# 3_channel_relay.net
KiCad netlist of a schematic drawn in Altium Designer
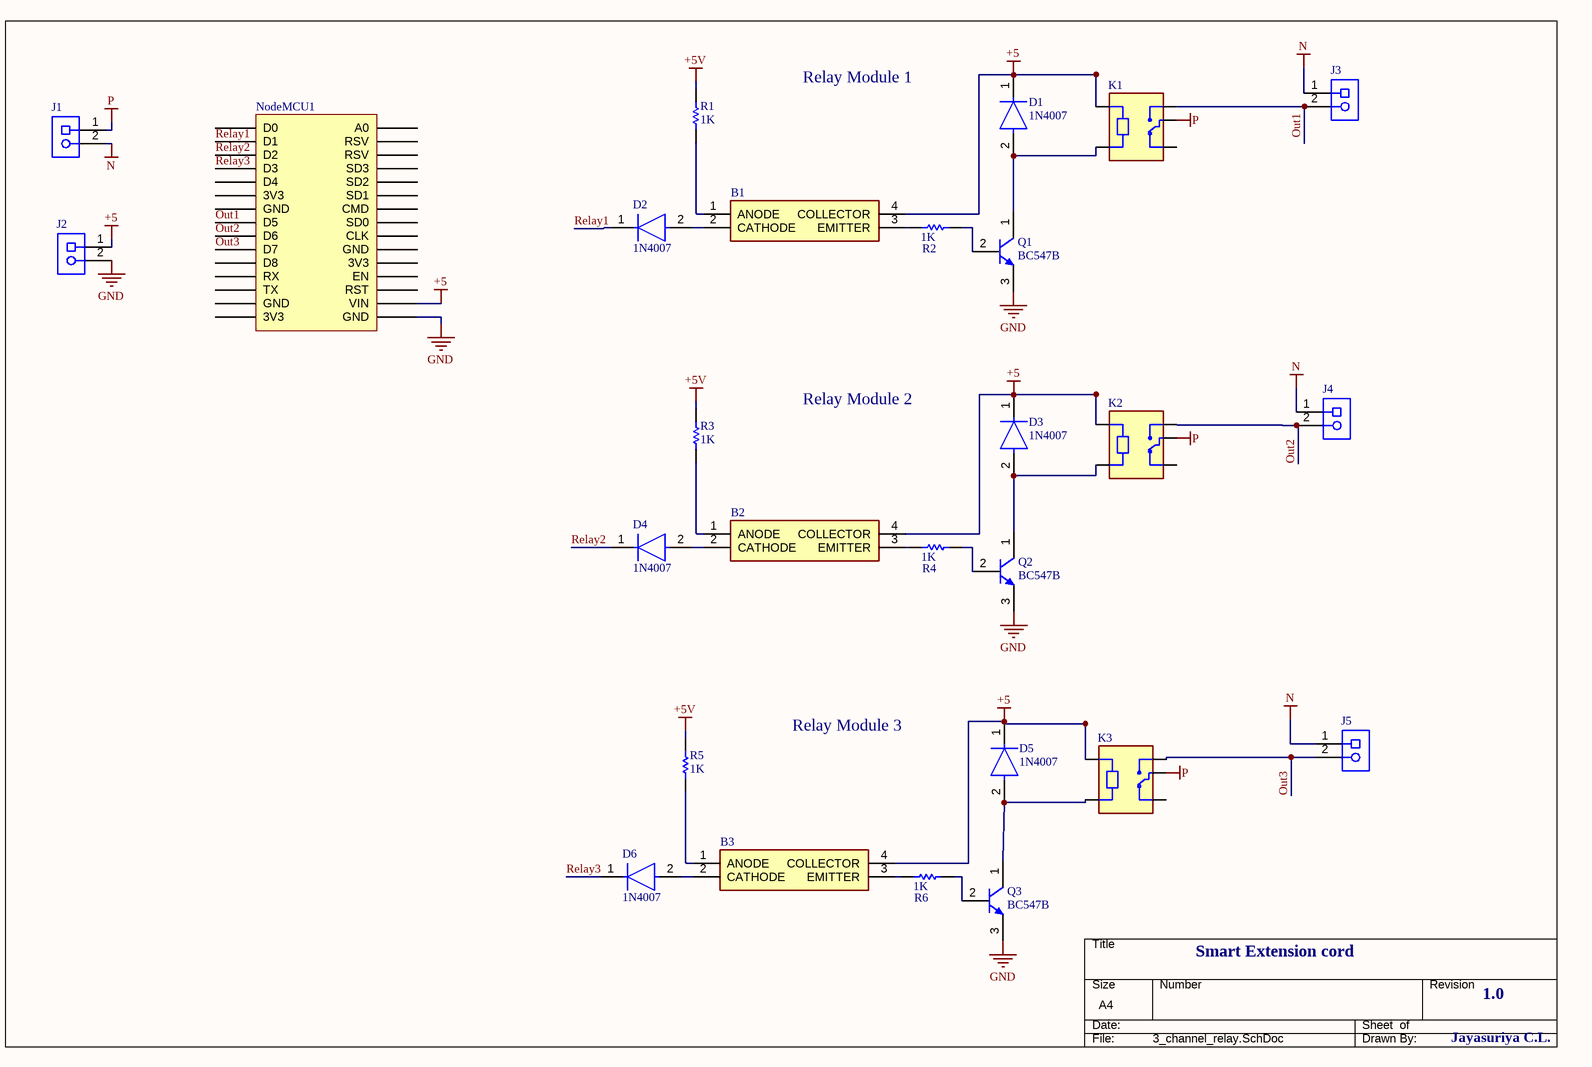
[diagram p0: 3_channel_relay.SchDoc]

(export (version "E")
  (design (tool "Eeschema 10.0.6"))
  (components
    (comp (ref "B1")
      (value "PC817X2NSZ0F")
      (footprint "DIP762W60P254L458H400Q4N")
      (libsource (lib "PC817X2NSZ0F") (part "PC817X2NSZ0F"))
    )
    (comp (ref "B2")
      (value "PC817X2NSZ0F")
      (footprint "DIP762W60P254L458H400Q4N")
      (libsource (lib "PC817X2NSZ0F") (part "PC817X2NSZ0F"))
    )
    (comp (ref "B3")
      (value "PC817X2NSZ0F")
      (footprint "DIP762W60P254L458H400Q4N")
      (libsource (lib "PC817X2NSZ0F") (part "PC817X2NSZ0F"))
    )
    (comp (ref "D1")
      (value "1N4007")
      (footprint "FP-1N4007-MFG")
      (description "Rectifier diode 1000 V 1 A DO-41, ,")
      (fields
        (field (name "MANUFACTURER") "Diotec")
        (field (name "OCTOPART") "https://octopart.com/1n4007-diotec-4040411")
      )
      (libsource (lib "Altium Content Vault") (part "d7152d700b627762746794eb795d46e"))
    )
    (comp (ref "D2")
      (value "1N4007")
      (footprint "FP-1N4007-MFG")
      (description "Rectifier diode 1000 V 1 A DO-41, ,")
      (fields
        (field (name "MANUFACTURER") "Diotec")
        (field (name "OCTOPART") "https://octopart.com/1n4007-diotec-4040411")
      )
      (libsource (lib "Altium Content Vault") (part "d7152d700b627762746794eb795d46e"))
    )
    (comp (ref "D3")
      (value "1N4007")
      (footprint "FP-1N4007-MFG")
      (description "Rectifier diode 1000 V 1 A DO-41, ,")
      (fields
        (field (name "MANUFACTURER") "Diotec")
        (field (name "OCTOPART") "https://octopart.com/1n4007-diotec-4040411")
      )
      (libsource (lib "Altium Content Vault") (part "d7152d700b627762746794eb795d46e"))
    )
    (comp (ref "D4")
      (value "1N4007")
      (footprint "FP-1N4007-MFG")
      (description "Rectifier diode 1000 V 1 A DO-41, ,")
      (fields
        (field (name "MANUFACTURER") "Diotec")
        (field (name "OCTOPART") "https://octopart.com/1n4007-diotec-4040411")
      )
      (libsource (lib "Altium Content Vault") (part "d7152d700b627762746794eb795d46e"))
    )
    (comp (ref "D5")
      (value "1N4007")
      (footprint "FP-1N4007-MFG")
      (description "Rectifier diode 1000 V 1 A DO-41, ,")
      (fields
        (field (name "MANUFACTURER") "Diotec")
        (field (name "OCTOPART") "https://octopart.com/1n4007-diotec-4040411")
      )
      (libsource (lib "Altium Content Vault") (part "d7152d700b627762746794eb795d46e"))
    )
    (comp (ref "D6")
      (value "1N4007")
      (footprint "FP-1N4007-MFG")
      (description "Rectifier diode 1000 V 1 A DO-41, ,")
      (fields
        (field (name "MANUFACTURER") "Diotec")
        (field (name "OCTOPART") "https://octopart.com/1n4007-diotec-4040411")
      )
      (libsource (lib "Altium Content Vault") (part "d7152d700b627762746794eb795d46e"))
    )
    (comp (ref "J1")
      (value "1729128")
      (footprint "PHOE-1729128-2_V")
      (description "PCB Terminal Block, 13.5 A, 400 V, 2-Pin THD, RoHS, Bulk")
      (fields (field (name "MANUFACTURER") "Phoenix Contact"))
      (libsource (lib "Altium Content Vault") (part "CN-2P-F-R2"))
    )
    (comp (ref "J2")
      (value "~")
      (footprint "PHOE-1729128-2_V")
      (description "PCB Terminal Block, 13.5 A, 400 V, 2-Pin THD, RoHS, Bulk")
      (fields (field (name "PARTNUMBER") "1729128") (field (name "MANUFACTURER") "Phoenix Contact"))
      (libsource (lib "Altium Content Vault") (part "CN-2P-F-R2"))
    )
    (comp (ref "J3")
      (value "1729128")
      (footprint "PHOE-1729128-2_V")
      (description "PCB Terminal Block, 13.5 A, 400 V, 2-Pin THD, RoHS, Bulk")
      (fields (field (name "MANUFACTURER") "Phoenix Contact"))
      (libsource (lib "") (part "CN-2P-F-R2_1"))
    )
    (comp (ref "J4")
      (value "1729128")
      (footprint "PHOE-1729128-2_V")
      (description "PCB Terminal Block, 13.5 A, 400 V, 2-Pin THD, RoHS, Bulk")
      (fields (field (name "MANUFACTURER") "Phoenix Contact"))
      (libsource (lib "") (part "CN-2P-F-R2_1"))
    )
    (comp (ref "J5")
      (value "1729128")
      (footprint "PHOE-1729128-2_V")
      (description "PCB Terminal Block, 13.5 A, 400 V, 2-Pin THD, RoHS, Bulk")
      (fields (field (name "MANUFACTURER") "Phoenix Contact"))
      (libsource (lib "") (part "CN-2P-F-R2_1"))
    )
    (comp (ref "K1")
      (value "SRD-05VDC-SL-C")
      (footprint "RELAY_SRD-05VDC-SL-C")
      (fields (field (name "MF") "Songle Relay"))
      (libsource (lib "SRD-05VDC-SL-C") (part "SRD-05VDC-SL-C"))
    )
    (comp (ref "K2")
      (value "SRD-05VDC-SL-C")
      (footprint "RELAY_SRD-05VDC-SL-C")
      (fields (field (name "MF") "Songle Relay"))
      (libsource (lib "SRD-05VDC-SL-C") (part "SRD-05VDC-SL-C"))
    )
    (comp (ref "K3")
      (value "SRD-05VDC-SL-C")
      (footprint "RELAY_SRD-05VDC-SL-C")
      (fields (field (name "MF") "Songle Relay"))
      (libsource (lib "SRD-05VDC-SL-C") (part "SRD-05VDC-SL-C"))
    )
    (comp (ref "NodeMCU1")
      (value "NodeMCU V1.0 ESP-12E")
      (footprint "NodeMCU V1.0 ESP-12E")
      (description "NodeMCU V1.0 ESP8266 (ESP-12E)")
      (libsource (lib "nodemcu") (part "NodeMCU V1.0 ESP-12E"))
    )
    (comp (ref "Q1")
      (value "BC547B")
      (footprint "ONSC-TO-92-3-29-11")
      (description "Amplifier Transistor, NPN Silicon, 3-Pin TO-92, Bulk Box")
      (fields (field (name "MANUFACTURER") "On Semiconductor"))
      (libsource (lib "Altium Content Vault") (part "ONSC-NPN-C1B2E3-3"))
    )
    (comp (ref "Q2")
      (value "BC547B")
      (footprint "ONSC-TO-92-3-29-11")
      (description "Amplifier Transistor, NPN Silicon, 3-Pin TO-92, Bulk Box")
      (fields (field (name "MANUFACTURER") "On Semiconductor"))
      (libsource (lib "Altium Content Vault") (part "ONSC-NPN-C1B2E3-3"))
    )
    (comp (ref "Q3")
      (value "BC547B")
      (footprint "ONSC-TO-92-3-29-11")
      (description "Amplifier Transistor, NPN Silicon, 3-Pin TO-92, Bulk Box")
      (fields (field (name "MANUFACTURER") "On Semiconductor"))
      (libsource (lib "Altium Content Vault") (part "ONSC-NPN-C1B2E3-3"))
    )
    (comp (ref "R1")
      (value "1K")
      (footprint "RESA60-630X240")
      (description "Axial Resistor, 1 KOhm, +/- 1%, 250 mW, -55 to 155 degC, 2-Pin THD, RoHS, Bulk")
      (fields (field (name "TOLERANCE") "1%"))
      (libsource (lib "Altium Content Vault") (part "RES-2"))
    )
    (comp (ref "R2")
      (value "1K")
      (footprint "RESA60-630X240")
      (description "Axial Resistor, 1 KOhm, +/- 1%, 250 mW, -55 to 155 degC, 2-Pin THD, RoHS, Bulk")
      (fields (field (name "TOLERANCE") "1%"))
      (libsource (lib "Altium Content Vault") (part "RES-2"))
    )
    (comp (ref "R3")
      (value "1K")
      (footprint "RESA60-630X240")
      (description "Axial Resistor, 1 KOhm, +/- 1%, 250 mW, -55 to 155 degC, 2-Pin THD, RoHS, Bulk")
      (fields (field (name "TOLERANCE") "1%"))
      (libsource (lib "Altium Content Vault") (part "RES-2"))
    )
    (comp (ref "R4")
      (value "1K")
      (footprint "RESA60-630X240")
      (description "Axial Resistor, 1 KOhm, +/- 1%, 250 mW, -55 to 155 degC, 2-Pin THD, RoHS, Bulk")
      (fields (field (name "TOLERANCE") "1%"))
      (libsource (lib "Altium Content Vault") (part "RES-2"))
    )
    (comp (ref "R5")
      (value "1K")
      (footprint "RESA60-630X240")
      (description "Axial Resistor, 1 KOhm, +/- 1%, 250 mW, -55 to 155 degC, 2-Pin THD, RoHS, Bulk")
      (fields (field (name "TOLERANCE") "1%"))
      (libsource (lib "Altium Content Vault") (part "RES-2"))
    )
    (comp (ref "R6")
      (value "1K")
      (footprint "RESA60-630X240")
      (description "Axial Resistor, 1 KOhm, +/- 1%, 250 mW, -55 to 155 degC, 2-Pin THD, RoHS, Bulk")
      (fields (field (name "TOLERANCE") "1%"))
      (libsource (lib "Altium Content Vault") (part "RES-2"))
    )
  )
  (nets
    (net (code "1") (name "+5") (class "Default")
      (node (ref "B1") (pin "4") (pinfunction "COLLECTOR_4") (pintype "passive"))
      (node (ref "B2") (pin "4") (pinfunction "COLLECTOR_4") (pintype "passive"))
      (node (ref "B3") (pin "4") (pinfunction "COLLECTOR_4") (pintype "passive"))
      (node (ref "D1") (pin "1") (pinfunction "C_1") (pintype "passive"))
      (node (ref "D3") (pin "1") (pinfunction "C_1") (pintype "passive"))
      (node (ref "D5") (pin "1") (pinfunction "C_1") (pintype "passive"))
      (node (ref "J2") (pin "1") (pinfunction "1_1") (pintype "passive"))
      (node (ref "K1") (pin "A1") (pinfunction "A1_A1") (pintype "passive"))
      (node (ref "K2") (pin "A1") (pinfunction "A1_A1") (pintype "passive"))
      (node (ref "K3") (pin "A1") (pinfunction "A1_A1") (pintype "passive"))
      (node (ref "NodeMCU1") (pin "VIN") (pinfunction "VIN_VIN") (pintype "passive"))
    )
    (net (code "2") (name "+5V") (class "Default")
      (node (ref "R1") (pin "2") (pinfunction "2_2") (pintype "passive"))
      (node (ref "R3") (pin "2") (pinfunction "2_2") (pintype "passive"))
      (node (ref "R5") (pin "2") (pinfunction "2_2") (pintype "passive"))
    )
    (net (code "3") (name "/Out1") (class "Default")
      (node (ref "J3") (pin "2") (pinfunction "2_2") (pintype "passive"))
      (node (ref "K1") (pin "NC") (pinfunction "NC_NC") (pintype "passive"))
      (node (ref "NodeMCU1") (pin "D5") (pinfunction "D5_D5") (pintype "passive"))
    )
    (net (code "4") (name "/Out2") (class "Default")
      (node (ref "J4") (pin "2") (pinfunction "2_2") (pintype "passive"))
      (node (ref "K2") (pin "NC") (pinfunction "NC_NC") (pintype "passive"))
      (node (ref "NodeMCU1") (pin "D6") (pinfunction "D6_D6") (pintype "passive"))
    )
    (net (code "5") (name "/Out3") (class "Default")
      (node (ref "J5") (pin "2") (pinfunction "2_2") (pintype "passive"))
      (node (ref "K3") (pin "NC") (pinfunction "NC_NC") (pintype "passive"))
      (node (ref "NodeMCU1") (pin "D7") (pinfunction "D7_D7") (pintype "passive"))
    )
    (net (code "6") (name "/Relay1") (class "Default")
      (node (ref "D2") (pin "1") (pinfunction "C_1") (pintype "passive"))
      (node (ref "NodeMCU1") (pin "D1") (pinfunction "D1_D1") (pintype "passive"))
    )
    (net (code "7") (name "/Relay2") (class "Default")
      (node (ref "D4") (pin "1") (pinfunction "C_1") (pintype "passive"))
      (node (ref "NodeMCU1") (pin "D2") (pinfunction "D2_D2") (pintype "passive"))
    )
    (net (code "8") (name "/Relay3") (class "Default")
      (node (ref "D6") (pin "1") (pinfunction "C_1") (pintype "passive"))
      (node (ref "NodeMCU1") (pin "D3") (pinfunction "D3_D3") (pintype "passive"))
    )
    (net (code "9") (name "GND") (class "Default")
      (node (ref "J2") (pin "2") (pinfunction "2_2") (pintype "passive"))
      (node (ref "NodeMCU1") (pin "GND") (pinfunction "GND_GND") (pintype "passive"))
      (node (ref "Q1") (pin "3") (pinfunction "E_3") (pintype "passive"))
      (node (ref "Q2") (pin "3") (pinfunction "E_3") (pintype "passive"))
      (node (ref "Q3") (pin "3") (pinfunction "E_3") (pintype "passive"))
    )
    (net (code "10") (name "N") (class "Default")
      (node (ref "J1") (pin "2") (pinfunction "2_2") (pintype "passive"))
      (node (ref "J3") (pin "1") (pinfunction "1_1") (pintype "passive"))
      (node (ref "J4") (pin "1") (pinfunction "1_1") (pintype "passive"))
      (node (ref "J5") (pin "1") (pinfunction "1_1") (pintype "passive"))
    )
    (net (code "11") (name "Net-(B1-ANODE)") (class "Default")
      (node (ref "B1") (pin "1") (pinfunction "ANODE_1") (pintype "passive"))
      (node (ref "R1") (pin "1") (pinfunction "1_1") (pintype "passive"))
    )
    (net (code "12") (name "Net-(B1-CATHODE)") (class "Default")
      (node (ref "B1") (pin "2") (pinfunction "CATHODE_2") (pintype "passive"))
      (node (ref "D2") (pin "2") (pinfunction "A_2") (pintype "passive"))
    )
    (net (code "13") (name "Net-(B1-EMITTER)") (class "Default")
      (node (ref "B1") (pin "3") (pinfunction "EMITTER_3") (pintype "passive"))
      (node (ref "R2") (pin "2") (pinfunction "2_2") (pintype "passive"))
    )
    (net (code "14") (name "Net-(B2-ANODE)") (class "Default")
      (node (ref "B2") (pin "1") (pinfunction "ANODE_1") (pintype "passive"))
      (node (ref "R3") (pin "1") (pinfunction "1_1") (pintype "passive"))
    )
    (net (code "15") (name "Net-(B2-CATHODE)") (class "Default")
      (node (ref "B2") (pin "2") (pinfunction "CATHODE_2") (pintype "passive"))
      (node (ref "D4") (pin "2") (pinfunction "A_2") (pintype "passive"))
    )
    (net (code "16") (name "Net-(B2-EMITTER)") (class "Default")
      (node (ref "B2") (pin "3") (pinfunction "EMITTER_3") (pintype "passive"))
      (node (ref "R4") (pin "2") (pinfunction "2_2") (pintype "passive"))
    )
    (net (code "17") (name "Net-(B3-ANODE)") (class "Default")
      (node (ref "B3") (pin "1") (pinfunction "ANODE_1") (pintype "passive"))
      (node (ref "R5") (pin "1") (pinfunction "1_1") (pintype "passive"))
    )
    (net (code "18") (name "Net-(B3-CATHODE)") (class "Default")
      (node (ref "B3") (pin "2") (pinfunction "CATHODE_2") (pintype "passive"))
      (node (ref "D6") (pin "2") (pinfunction "A_2") (pintype "passive"))
    )
    (net (code "19") (name "Net-(B3-EMITTER)") (class "Default")
      (node (ref "B3") (pin "3") (pinfunction "EMITTER_3") (pintype "passive"))
      (node (ref "R6") (pin "2") (pinfunction "2_2") (pintype "passive"))
    )
    (net (code "20") (name "Net-(D1-A)") (class "Default")
      (node (ref "D1") (pin "2") (pinfunction "A_2") (pintype "passive"))
      (node (ref "K1") (pin "A2") (pinfunction "A2_A2") (pintype "passive"))
      (node (ref "Q1") (pin "1") (pinfunction "C_1") (pintype "passive"))
    )
    (net (code "21") (name "Net-(D3-A)") (class "Default")
      (node (ref "D3") (pin "2") (pinfunction "A_2") (pintype "passive"))
      (node (ref "K2") (pin "A2") (pinfunction "A2_A2") (pintype "passive"))
      (node (ref "Q2") (pin "1") (pinfunction "C_1") (pintype "passive"))
    )
    (net (code "22") (name "Net-(D5-A)") (class "Default")
      (node (ref "D5") (pin "2") (pinfunction "A_2") (pintype "passive"))
      (node (ref "K3") (pin "A2") (pinfunction "A2_A2") (pintype "passive"))
      (node (ref "Q3") (pin "1") (pinfunction "C_1") (pintype "passive"))
    )
    (net (code "23") (name "Net-(Q1-B)") (class "Default")
      (node (ref "Q1") (pin "2") (pinfunction "B_2") (pintype "passive"))
      (node (ref "R2") (pin "1") (pinfunction "1_1") (pintype "passive"))
    )
    (net (code "24") (name "Net-(Q2-B)") (class "Default")
      (node (ref "Q2") (pin "2") (pinfunction "B_2") (pintype "passive"))
      (node (ref "R4") (pin "1") (pinfunction "1_1") (pintype "passive"))
    )
    (net (code "25") (name "Net-(Q3-B)") (class "Default")
      (node (ref "Q3") (pin "2") (pinfunction "B_2") (pintype "passive"))
      (node (ref "R6") (pin "1") (pinfunction "1_1") (pintype "passive"))
    )
    (net (code "26") (name "P") (class "Default")
      (node (ref "J1") (pin "1") (pinfunction "1_1") (pintype "passive"))
      (node (ref "K1") (pin "COM") (pinfunction "COM_COM") (pintype "passive"))
      (node (ref "K2") (pin "COM") (pinfunction "COM_COM") (pintype "passive"))
      (node (ref "K3") (pin "COM") (pinfunction "COM_COM") (pintype "passive"))
    )
    (net (code "27") (name "unconnected-(K1-PadNO)") (class "Default")
      (node (ref "K1") (pin "NO") (pinfunction "NO_NO") (pintype "passive"))
    )
    (net (code "28") (name "unconnected-(K2-PadNO)") (class "Default")
      (node (ref "K2") (pin "NO") (pinfunction "NO_NO") (pintype "passive"))
    )
    (net (code "29") (name "unconnected-(K3-PadNO)") (class "Default")
      (node (ref "K3") (pin "NO") (pinfunction "NO_NO") (pintype "passive"))
    )
    (net (code "30") (name "unconnected-(NodeMCU1-Pad3V3)") (class "Default")
      (node (ref "NodeMCU1") (pin "3V3") (pinfunction "3V3_3V3") (pintype "passive"))
    )
    (net (code "31") (name "unconnected-(NodeMCU1-Pad3V3)_1") (class "Default")
      (node (ref "NodeMCU1") (pin "3V3") (pinfunction "3V3_3V3") (pintype "passive"))
    )
    (net (code "32") (name "unconnected-(NodeMCU1-Pad3V3)_2") (class "Default")
      (node (ref "NodeMCU1") (pin "3V3") (pinfunction "3V3_3V3") (pintype "passive"))
    )
    (net (code "33") (name "unconnected-(NodeMCU1-PadA0)") (class "Default")
      (node (ref "NodeMCU1") (pin "A0") (pinfunction "A0_A0") (pintype "passive"))
    )
    (net (code "34") (name "unconnected-(NodeMCU1-PadCLK)") (class "Default")
      (node (ref "NodeMCU1") (pin "CLK") (pinfunction "CLK_CLK") (pintype "passive"))
    )
    (net (code "35") (name "unconnected-(NodeMCU1-PadCMD)") (class "Default")
      (node (ref "NodeMCU1") (pin "CMD") (pinfunction "CMD_CMD") (pintype "passive"))
    )
    (net (code "36") (name "unconnected-(NodeMCU1-PadD0)") (class "Default")
      (node (ref "NodeMCU1") (pin "D0") (pinfunction "D0_D0") (pintype "passive"))
    )
    (net (code "37") (name "unconnected-(NodeMCU1-PadD4)") (class "Default")
      (node (ref "NodeMCU1") (pin "D4") (pinfunction "D4_D4") (pintype "passive"))
    )
    (net (code "38") (name "unconnected-(NodeMCU1-PadD8)") (class "Default")
      (node (ref "NodeMCU1") (pin "D8") (pinfunction "D8_D8") (pintype "passive"))
    )
    (net (code "39") (name "unconnected-(NodeMCU1-PadEN)") (class "Default")
      (node (ref "NodeMCU1") (pin "EN") (pinfunction "EN_EN") (pintype "passive"))
    )
    (net (code "40") (name "unconnected-(NodeMCU1-PadGND)") (class "Default")
      (node (ref "NodeMCU1") (pin "GND") (pinfunction "GND_GND") (pintype "passive"))
    )
    (net (code "41") (name "unconnected-(NodeMCU1-PadGND)_1") (class "Default")
      (node (ref "NodeMCU1") (pin "GND") (pinfunction "GND_GND") (pintype "passive"))
    )
    (net (code "42") (name "unconnected-(NodeMCU1-PadGND)_2") (class "Default")
      (node (ref "NodeMCU1") (pin "GND") (pinfunction "GND_GND") (pintype "passive"))
    )
    (net (code "43") (name "unconnected-(NodeMCU1-PadRST)") (class "Default")
      (node (ref "NodeMCU1") (pin "RST") (pinfunction "RST_RST") (pintype "passive"))
    )
    (net (code "44") (name "unconnected-(NodeMCU1-PadRSV)") (class "Default")
      (node (ref "NodeMCU1") (pin "RSV") (pinfunction "RSV_RSV") (pintype "passive"))
    )
    (net (code "45") (name "unconnected-(NodeMCU1-PadRSV)_1") (class "Default")
      (node (ref "NodeMCU1") (pin "RSV") (pinfunction "RSV_RSV") (pintype "passive"))
    )
    (net (code "46") (name "unconnected-(NodeMCU1-PadRX)") (class "Default")
      (node (ref "NodeMCU1") (pin "RX") (pinfunction "RX_RX") (pintype "passive"))
    )
    (net (code "47") (name "unconnected-(NodeMCU1-PadSD0)") (class "Default")
      (node (ref "NodeMCU1") (pin "SD0") (pinfunction "SD0_SD0") (pintype "passive"))
    )
    (net (code "48") (name "unconnected-(NodeMCU1-PadSD1)") (class "Default")
      (node (ref "NodeMCU1") (pin "SD1") (pinfunction "SD1_SD1") (pintype "passive"))
    )
    (net (code "49") (name "unconnected-(NodeMCU1-PadSD2)") (class "Default")
      (node (ref "NodeMCU1") (pin "SD2") (pinfunction "SD2_SD2") (pintype "passive"))
    )
    (net (code "50") (name "unconnected-(NodeMCU1-PadSD3)") (class "Default")
      (node (ref "NodeMCU1") (pin "SD3") (pinfunction "SD3_SD3") (pintype "passive"))
    )
    (net (code "51") (name "unconnected-(NodeMCU1-PadTX)") (class "Default")
      (node (ref "NodeMCU1") (pin "TX") (pinfunction "TX_TX") (pintype "passive"))
    )
  )
)
